# espower.net
KiCad netlist of a schematic drawn in EAGLE
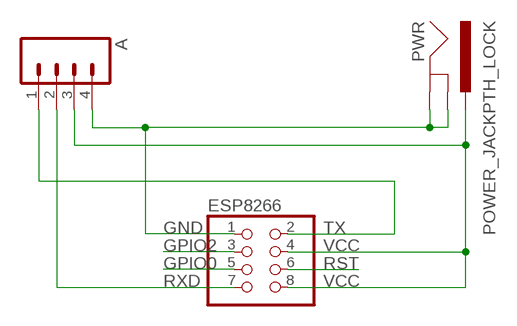
[diagram p0: schematic, sheet 1]

(export (version "E")
  (design (tool "Eeschema 10.0.6"))
  (components
    (comp (ref "A")
      (value "M04PTH")
      (footprint "eagle-import:1X04")
      (libsource (lib "eagle-import") (part "M04PTH"))
    )
    (comp (ref "ESP8266")
      (value "PINHD-2X4")
      (footprint "eagle-import:2X04")
      (libsource (lib "eagle-import") (part "PINHD-2X4"))
    )
    (comp (ref "PWR")
      (value "POWER_JACKPTH_LOCK")
      (footprint "eagle-import:POWER_JACK_PTH_LOCK")
      (libsource (lib "eagle-import") (part "POWER_JACKPTH_LOCK"))
    )
  )
  (nets
    (net (code "1") (name "/GND") (class "Default")
      (node (ref "A") (pin "4") (pinfunction "4_4") (pintype "passive"))
      (node (ref "ESP8266") (pin "1") (pinfunction "1_1") (pintype "passive"))
      (node (ref "PWR") (pin "GND") (pinfunction "GND_GND") (pintype "bidirectional"))
      (node (ref "PWR") (pin "GNDBREAK") (pinfunction "GNDBREAK_GNDBREAK") (pintype "bidirectional"))
    )
    (net (code "2") (name "/GPIO0") (class "Default")
      (node (ref "ESP8266") (pin "5") (pinfunction "5_5") (pintype "passive"))
    )
    (net (code "3") (name "/GPIO2") (class "Default")
      (node (ref "ESP8266") (pin "3") (pinfunction "3_3") (pintype "passive"))
    )
    (net (code "4") (name "/RST") (class "Default")
      (node (ref "ESP8266") (pin "6") (pinfunction "6_6") (pintype "passive"))
    )
    (net (code "5") (name "/RXD") (class "Default")
      (node (ref "A") (pin "2") (pinfunction "2_2") (pintype "passive"))
      (node (ref "ESP8266") (pin "7") (pinfunction "7_7") (pintype "passive"))
    )
    (net (code "6") (name "/TX") (class "Default")
      (node (ref "A") (pin "1") (pinfunction "1_1") (pintype "passive"))
      (node (ref "ESP8266") (pin "2") (pinfunction "2_2") (pintype "passive"))
    )
    (net (code "7") (name "/VCC") (class "Default")
      (node (ref "A") (pin "3") (pinfunction "3_3") (pintype "passive"))
      (node (ref "ESP8266") (pin "4") (pinfunction "4_4") (pintype "passive"))
      (node (ref "ESP8266") (pin "8") (pinfunction "8_8") (pintype "passive"))
      (node (ref "PWR") (pin "PWR") (pinfunction "PWR_PWR") (pintype "bidirectional"))
    )
  )
)
